# Front_Connector.net
KiCad netlist of a schematic drawn in Altium Designer
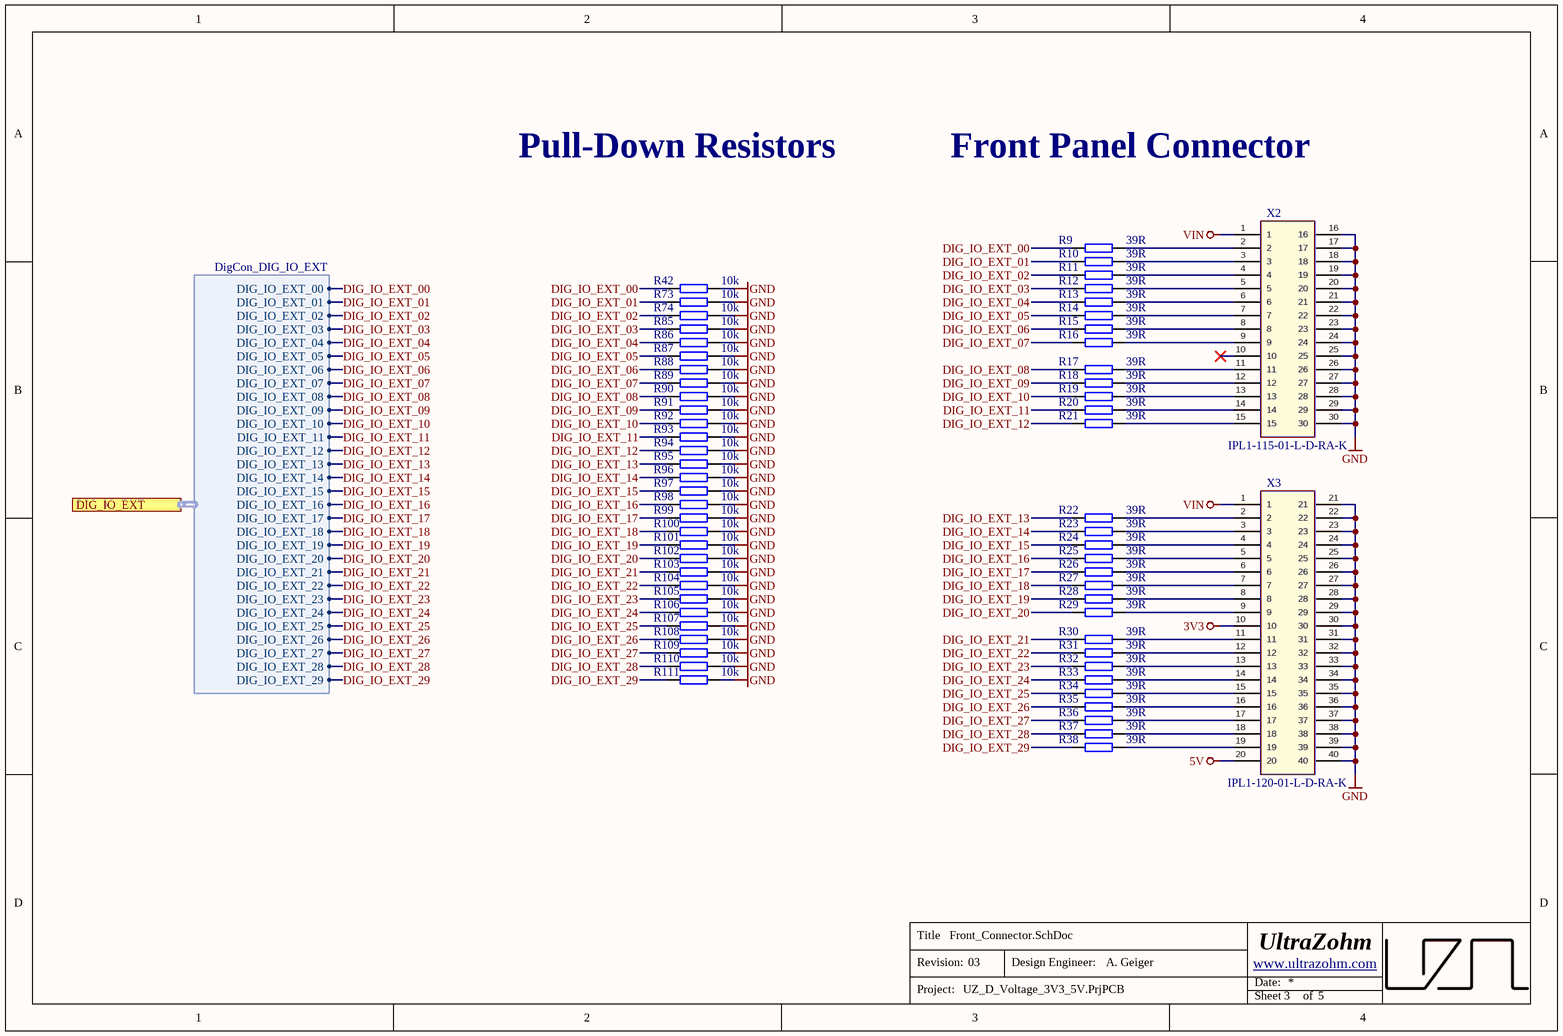
[diagram p0: Front_Connector.SchDoc]

(export (version "E")
  (design (tool "Eeschema 10.0.6"))
  (components
    (comp (ref "R9")
      (value "39R")
      (footprint "R_0603_TE")
      (description "Generic resistor")
      (fields
        (field (name "MANUFACTURER PART NUMBER") "UZgen_R_0603_39R")
        (field (name "MANUFACTURER") "UZgen")
        (field (name "CREATED FROM") "UZgenTool")
      )
      (libsource (lib "user") (part "RES"))
    )
    (comp (ref "R10")
      (value "39R")
      (footprint "R_0603_TE")
      (description "Generic resistor")
      (fields
        (field (name "MANUFACTURER PART NUMBER") "UZgen_R_0603_39R")
        (field (name "MANUFACTURER") "UZgen")
        (field (name "CREATED FROM") "UZgenTool")
      )
      (libsource (lib "user") (part "RES"))
    )
    (comp (ref "R11")
      (value "39R")
      (footprint "R_0603_TE")
      (description "Generic resistor")
      (fields
        (field (name "MANUFACTURER PART NUMBER") "UZgen_R_0603_39R")
        (field (name "MANUFACTURER") "UZgen")
        (field (name "CREATED FROM") "UZgenTool")
      )
      (libsource (lib "user") (part "RES"))
    )
    (comp (ref "R12")
      (value "39R")
      (footprint "R_0603_TE")
      (description "Generic resistor")
      (fields
        (field (name "MANUFACTURER PART NUMBER") "UZgen_R_0603_39R")
        (field (name "MANUFACTURER") "UZgen")
        (field (name "CREATED FROM") "UZgenTool")
      )
      (libsource (lib "user") (part "RES"))
    )
    (comp (ref "R13")
      (value "39R")
      (footprint "R_0603_TE")
      (description "Generic resistor")
      (fields
        (field (name "MANUFACTURER PART NUMBER") "UZgen_R_0603_39R")
        (field (name "MANUFACTURER") "UZgen")
        (field (name "CREATED FROM") "UZgenTool")
      )
      (libsource (lib "user") (part "RES"))
    )
    (comp (ref "R14")
      (value "39R")
      (footprint "R_0603_TE")
      (description "Generic resistor")
      (fields
        (field (name "MANUFACTURER PART NUMBER") "UZgen_R_0603_39R")
        (field (name "MANUFACTURER") "UZgen")
        (field (name "CREATED FROM") "UZgenTool")
      )
      (libsource (lib "user") (part "RES"))
    )
    (comp (ref "R15")
      (value "39R")
      (footprint "R_0603_TE")
      (description "Generic resistor")
      (fields
        (field (name "MANUFACTURER PART NUMBER") "UZgen_R_0603_39R")
        (field (name "MANUFACTURER") "UZgen")
        (field (name "CREATED FROM") "UZgenTool")
      )
      (libsource (lib "user") (part "RES"))
    )
    (comp (ref "R16")
      (value "39R")
      (footprint "R_0603_TE")
      (description "Generic resistor")
      (fields
        (field (name "MANUFACTURER PART NUMBER") "UZgen_R_0603_39R")
        (field (name "MANUFACTURER") "UZgen")
        (field (name "CREATED FROM") "UZgenTool")
      )
      (libsource (lib "user") (part "RES"))
    )
    (comp (ref "R17")
      (value "39R")
      (footprint "R_0603_TE")
      (description "Generic resistor")
      (fields
        (field (name "MANUFACTURER PART NUMBER") "UZgen_R_0603_39R")
        (field (name "MANUFACTURER") "UZgen")
        (field (name "CREATED FROM") "UZgenTool")
      )
      (libsource (lib "user") (part "RES"))
    )
    (comp (ref "R18")
      (value "39R")
      (footprint "R_0603_TE")
      (description "Generic resistor")
      (fields
        (field (name "MANUFACTURER PART NUMBER") "UZgen_R_0603_39R")
        (field (name "MANUFACTURER") "UZgen")
        (field (name "CREATED FROM") "UZgenTool")
      )
      (libsource (lib "user") (part "RES"))
    )
    (comp (ref "R19")
      (value "39R")
      (footprint "R_0603_TE")
      (description "Generic resistor")
      (fields
        (field (name "MANUFACTURER PART NUMBER") "UZgen_R_0603_39R")
        (field (name "MANUFACTURER") "UZgen")
        (field (name "CREATED FROM") "UZgenTool")
      )
      (libsource (lib "user") (part "RES"))
    )
    (comp (ref "R20")
      (value "39R")
      (footprint "R_0603_TE")
      (description "Generic resistor")
      (fields
        (field (name "MANUFACTURER PART NUMBER") "UZgen_R_0603_39R")
        (field (name "MANUFACTURER") "UZgen")
        (field (name "CREATED FROM") "UZgenTool")
      )
      (libsource (lib "user") (part "RES"))
    )
    (comp (ref "R21")
      (value "39R")
      (footprint "R_0603_TE")
      (description "Generic resistor")
      (fields
        (field (name "MANUFACTURER PART NUMBER") "UZgen_R_0603_39R")
        (field (name "MANUFACTURER") "UZgen")
        (field (name "CREATED FROM") "UZgenTool")
      )
      (libsource (lib "user") (part "RES"))
    )
    (comp (ref "R22")
      (value "39R")
      (footprint "R_0603_TE")
      (description "Generic resistor")
      (fields
        (field (name "MANUFACTURER PART NUMBER") "UZgen_R_0603_39R")
        (field (name "MANUFACTURER") "UZgen")
        (field (name "CREATED FROM") "UZgenTool")
      )
      (libsource (lib "user") (part "RES"))
    )
    (comp (ref "R23")
      (value "39R")
      (footprint "R_0603_TE")
      (description "Generic resistor")
      (fields
        (field (name "MANUFACTURER PART NUMBER") "UZgen_R_0603_39R")
        (field (name "MANUFACTURER") "UZgen")
        (field (name "CREATED FROM") "UZgenTool")
      )
      (libsource (lib "user") (part "RES"))
    )
    (comp (ref "R24")
      (value "39R")
      (footprint "R_0603_TE")
      (description "Generic resistor")
      (fields
        (field (name "MANUFACTURER PART NUMBER") "UZgen_R_0603_39R")
        (field (name "MANUFACTURER") "UZgen")
        (field (name "CREATED FROM") "UZgenTool")
      )
      (libsource (lib "user") (part "RES"))
    )
    (comp (ref "R25")
      (value "39R")
      (footprint "R_0603_TE")
      (description "Generic resistor")
      (fields
        (field (name "MANUFACTURER PART NUMBER") "UZgen_R_0603_39R")
        (field (name "MANUFACTURER") "UZgen")
        (field (name "CREATED FROM") "UZgenTool")
      )
      (libsource (lib "user") (part "RES"))
    )
    (comp (ref "R26")
      (value "39R")
      (footprint "R_0603_TE")
      (description "Generic resistor")
      (fields
        (field (name "MANUFACTURER PART NUMBER") "UZgen_R_0603_39R")
        (field (name "MANUFACTURER") "UZgen")
        (field (name "CREATED FROM") "UZgenTool")
      )
      (libsource (lib "user") (part "RES"))
    )
    (comp (ref "R27")
      (value "39R")
      (footprint "R_0603_TE")
      (description "Generic resistor")
      (fields
        (field (name "MANUFACTURER PART NUMBER") "UZgen_R_0603_39R")
        (field (name "MANUFACTURER") "UZgen")
        (field (name "CREATED FROM") "UZgenTool")
      )
      (libsource (lib "user") (part "RES"))
    )
    (comp (ref "R28")
      (value "39R")
      (footprint "R_0603_TE")
      (description "Generic resistor")
      (fields
        (field (name "MANUFACTURER PART NUMBER") "UZgen_R_0603_39R")
        (field (name "MANUFACTURER") "UZgen")
        (field (name "CREATED FROM") "UZgenTool")
      )
      (libsource (lib "user") (part "RES"))
    )
    (comp (ref "R29")
      (value "39R")
      (footprint "R_0603_TE")
      (description "Generic resistor")
      (fields
        (field (name "MANUFACTURER PART NUMBER") "UZgen_R_0603_39R")
        (field (name "MANUFACTURER") "UZgen")
        (field (name "CREATED FROM") "UZgenTool")
      )
      (libsource (lib "user") (part "RES"))
    )
    (comp (ref "R30")
      (value "39R")
      (footprint "R_0603_TE")
      (description "Generic resistor")
      (fields
        (field (name "MANUFACTURER PART NUMBER") "UZgen_R_0603_39R")
        (field (name "MANUFACTURER") "UZgen")
        (field (name "CREATED FROM") "UZgenTool")
      )
      (libsource (lib "user") (part "RES"))
    )
    (comp (ref "R31")
      (value "39R")
      (footprint "R_0603_TE")
      (description "Generic resistor")
      (fields
        (field (name "MANUFACTURER PART NUMBER") "UZgen_R_0603_39R")
        (field (name "MANUFACTURER") "UZgen")
        (field (name "CREATED FROM") "UZgenTool")
      )
      (libsource (lib "user") (part "RES"))
    )
    (comp (ref "R32")
      (value "39R")
      (footprint "R_0603_TE")
      (description "Generic resistor")
      (fields
        (field (name "MANUFACTURER PART NUMBER") "UZgen_R_0603_39R")
        (field (name "MANUFACTURER") "UZgen")
        (field (name "CREATED FROM") "UZgenTool")
      )
      (libsource (lib "user") (part "RES"))
    )
    (comp (ref "R33")
      (value "39R")
      (footprint "R_0603_TE")
      (description "Generic resistor")
      (fields
        (field (name "MANUFACTURER PART NUMBER") "UZgen_R_0603_39R")
        (field (name "MANUFACTURER") "UZgen")
        (field (name "CREATED FROM") "UZgenTool")
      )
      (libsource (lib "user") (part "RES"))
    )
    (comp (ref "R34")
      (value "39R")
      (footprint "R_0603_TE")
      (description "Generic resistor")
      (fields
        (field (name "MANUFACTURER PART NUMBER") "UZgen_R_0603_39R")
        (field (name "MANUFACTURER") "UZgen")
        (field (name "CREATED FROM") "UZgenTool")
      )
      (libsource (lib "user") (part "RES"))
    )
    (comp (ref "R35")
      (value "39R")
      (footprint "R_0603_TE")
      (description "Generic resistor")
      (fields
        (field (name "MANUFACTURER PART NUMBER") "UZgen_R_0603_39R")
        (field (name "MANUFACTURER") "UZgen")
        (field (name "CREATED FROM") "UZgenTool")
      )
      (libsource (lib "user") (part "RES"))
    )
    (comp (ref "R36")
      (value "39R")
      (footprint "R_0603_TE")
      (description "Generic resistor")
      (fields
        (field (name "MANUFACTURER PART NUMBER") "UZgen_R_0603_39R")
        (field (name "MANUFACTURER") "UZgen")
        (field (name "CREATED FROM") "UZgenTool")
      )
      (libsource (lib "user") (part "RES"))
    )
    (comp (ref "R37")
      (value "39R")
      (footprint "R_0603_TE")
      (description "Generic resistor")
      (fields
        (field (name "MANUFACTURER PART NUMBER") "UZgen_R_0603_39R")
        (field (name "MANUFACTURER") "UZgen")
        (field (name "CREATED FROM") "UZgenTool")
      )
      (libsource (lib "user") (part "RES"))
    )
    (comp (ref "R38")
      (value "39R")
      (footprint "R_0603_TE")
      (description "Generic resistor")
      (fields
        (field (name "MANUFACTURER PART NUMBER") "UZgen_R_0603_39R")
        (field (name "MANUFACTURER") "UZgen")
        (field (name "CREATED FROM") "UZgenTool")
      )
      (libsource (lib "user") (part "RES"))
    )
    (comp (ref "R42")
      (value "10k")
      (footprint "R_0603_TE")
      (description "Generic resistor")
      (fields
        (field (name "MANUFACTURER PART NUMBER") "UZgen_R_0603_10k")
        (field (name "MANUFACTURER") "UZgen")
        (field (name "CREATED FROM") "AGeiger")
      )
      (libsource (lib "user") (part "RES"))
    )
    (comp (ref "R73")
      (value "10k")
      (footprint "R_0603_TE")
      (description "Generic resistor")
      (fields
        (field (name "MANUFACTURER PART NUMBER") "UZgen_R_0603_10k")
        (field (name "MANUFACTURER") "UZgen")
        (field (name "CREATED FROM") "AGeiger")
      )
      (libsource (lib "user") (part "RES"))
    )
    (comp (ref "R74")
      (value "10k")
      (footprint "R_0603_TE")
      (description "Generic resistor")
      (fields
        (field (name "MANUFACTURER PART NUMBER") "UZgen_R_0603_10k")
        (field (name "MANUFACTURER") "UZgen")
        (field (name "CREATED FROM") "AGeiger")
      )
      (libsource (lib "user") (part "RES"))
    )
    (comp (ref "R85")
      (value "10k")
      (footprint "R_0603_TE")
      (description "Generic resistor")
      (fields
        (field (name "MANUFACTURER PART NUMBER") "UZgen_R_0603_10k")
        (field (name "MANUFACTURER") "UZgen")
        (field (name "CREATED FROM") "AGeiger")
      )
      (libsource (lib "user") (part "RES"))
    )
    (comp (ref "R86")
      (value "10k")
      (footprint "R_0603_TE")
      (description "Generic resistor")
      (fields
        (field (name "MANUFACTURER PART NUMBER") "UZgen_R_0603_10k")
        (field (name "MANUFACTURER") "UZgen")
        (field (name "CREATED FROM") "AGeiger")
      )
      (libsource (lib "user") (part "RES"))
    )
    (comp (ref "R87")
      (value "10k")
      (footprint "R_0603_TE")
      (description "Generic resistor")
      (fields
        (field (name "MANUFACTURER PART NUMBER") "UZgen_R_0603_10k")
        (field (name "MANUFACTURER") "UZgen")
        (field (name "CREATED FROM") "AGeiger")
      )
      (libsource (lib "user") (part "RES"))
    )
    (comp (ref "R88")
      (value "10k")
      (footprint "R_0603_TE")
      (description "Generic resistor")
      (fields
        (field (name "MANUFACTURER PART NUMBER") "UZgen_R_0603_10k")
        (field (name "MANUFACTURER") "UZgen")
        (field (name "CREATED FROM") "AGeiger")
      )
      (libsource (lib "user") (part "RES"))
    )
    (comp (ref "R89")
      (value "10k")
      (footprint "R_0603_TE")
      (description "Generic resistor")
      (fields
        (field (name "MANUFACTURER PART NUMBER") "UZgen_R_0603_10k")
        (field (name "MANUFACTURER") "UZgen")
        (field (name "CREATED FROM") "AGeiger")
      )
      (libsource (lib "user") (part "RES"))
    )
    (comp (ref "R90")
      (value "10k")
      (footprint "R_0603_TE")
      (description "Generic resistor")
      (fields
        (field (name "MANUFACTURER PART NUMBER") "UZgen_R_0603_10k")
        (field (name "MANUFACTURER") "UZgen")
        (field (name "CREATED FROM") "AGeiger")
      )
      (libsource (lib "user") (part "RES"))
    )
    (comp (ref "R91")
      (value "10k")
      (footprint "R_0603_TE")
      (description "Generic resistor")
      (fields
        (field (name "MANUFACTURER PART NUMBER") "UZgen_R_0603_10k")
        (field (name "MANUFACTURER") "UZgen")
        (field (name "CREATED FROM") "AGeiger")
      )
      (libsource (lib "user") (part "RES"))
    )
    (comp (ref "R92")
      (value "10k")
      (footprint "R_0603_TE")
      (description "Generic resistor")
      (fields
        (field (name "MANUFACTURER PART NUMBER") "UZgen_R_0603_10k")
        (field (name "MANUFACTURER") "UZgen")
        (field (name "CREATED FROM") "AGeiger")
      )
      (libsource (lib "user") (part "RES"))
    )
    (comp (ref "R93")
      (value "10k")
      (footprint "R_0603_TE")
      (description "Generic resistor")
      (fields
        (field (name "MANUFACTURER PART NUMBER") "UZgen_R_0603_10k")
        (field (name "MANUFACTURER") "UZgen")
        (field (name "CREATED FROM") "AGeiger")
      )
      (libsource (lib "user") (part "RES"))
    )
    (comp (ref "R94")
      (value "10k")
      (footprint "R_0603_TE")
      (description "Generic resistor")
      (fields
        (field (name "MANUFACTURER PART NUMBER") "UZgen_R_0603_10k")
        (field (name "MANUFACTURER") "UZgen")
        (field (name "CREATED FROM") "AGeiger")
      )
      (libsource (lib "user") (part "RES"))
    )
    (comp (ref "R95")
      (value "10k")
      (footprint "R_0603_TE")
      (description "Generic resistor")
      (fields
        (field (name "MANUFACTURER PART NUMBER") "UZgen_R_0603_10k")
        (field (name "MANUFACTURER") "UZgen")
        (field (name "CREATED FROM") "AGeiger")
      )
      (libsource (lib "user") (part "RES"))
    )
    (comp (ref "R96")
      (value "10k")
      (footprint "R_0603_TE")
      (description "Generic resistor")
      (fields
        (field (name "MANUFACTURER PART NUMBER") "UZgen_R_0603_10k")
        (field (name "MANUFACTURER") "UZgen")
        (field (name "CREATED FROM") "AGeiger")
      )
      (libsource (lib "user") (part "RES"))
    )
    (comp (ref "R97")
      (value "10k")
      (footprint "R_0603_TE")
      (description "Generic resistor")
      (fields
        (field (name "MANUFACTURER PART NUMBER") "UZgen_R_0603_10k")
        (field (name "MANUFACTURER") "UZgen")
        (field (name "CREATED FROM") "AGeiger")
      )
      (libsource (lib "user") (part "RES"))
    )
    (comp (ref "R98")
      (value "10k")
      (footprint "R_0603_TE")
      (description "Generic resistor")
      (fields
        (field (name "MANUFACTURER PART NUMBER") "UZgen_R_0603_10k")
        (field (name "MANUFACTURER") "UZgen")
        (field (name "CREATED FROM") "AGeiger")
      )
      (libsource (lib "user") (part "RES"))
    )
    (comp (ref "R99")
      (value "10k")
      (footprint "R_0603_TE")
      (description "Generic resistor")
      (fields
        (field (name "MANUFACTURER PART NUMBER") "UZgen_R_0603_10k")
        (field (name "MANUFACTURER") "UZgen")
        (field (name "CREATED FROM") "AGeiger")
      )
      (libsource (lib "user") (part "RES"))
    )
    (comp (ref "R100")
      (value "10k")
      (footprint "R_0603_TE")
      (description "Generic resistor")
      (fields
        (field (name "MANUFACTURER PART NUMBER") "UZgen_R_0603_10k")
        (field (name "MANUFACTURER") "UZgen")
        (field (name "CREATED FROM") "AGeiger")
      )
      (libsource (lib "user") (part "RES"))
    )
    (comp (ref "R101")
      (value "10k")
      (footprint "R_0603_TE")
      (description "Generic resistor")
      (fields
        (field (name "MANUFACTURER PART NUMBER") "UZgen_R_0603_10k")
        (field (name "MANUFACTURER") "UZgen")
        (field (name "CREATED FROM") "AGeiger")
      )
      (libsource (lib "user") (part "RES"))
    )
    (comp (ref "R102")
      (value "10k")
      (footprint "R_0603_TE")
      (description "Generic resistor")
      (fields
        (field (name "MANUFACTURER PART NUMBER") "UZgen_R_0603_10k")
        (field (name "MANUFACTURER") "UZgen")
        (field (name "CREATED FROM") "AGeiger")
      )
      (libsource (lib "user") (part "RES"))
    )
    (comp (ref "R103")
      (value "10k")
      (footprint "R_0603_TE")
      (description "Generic resistor")
      (fields
        (field (name "MANUFACTURER PART NUMBER") "UZgen_R_0603_10k")
        (field (name "MANUFACTURER") "UZgen")
        (field (name "CREATED FROM") "AGeiger")
      )
      (libsource (lib "user") (part "RES"))
    )
    (comp (ref "R104")
      (value "10k")
      (footprint "R_0603_TE")
      (description "Generic resistor")
      (fields
        (field (name "MANUFACTURER PART NUMBER") "UZgen_R_0603_10k")
        (field (name "MANUFACTURER") "UZgen")
        (field (name "CREATED FROM") "AGeiger")
      )
      (libsource (lib "user") (part "RES"))
    )
    (comp (ref "R105")
      (value "10k")
      (footprint "R_0603_TE")
      (description "Generic resistor")
      (fields
        (field (name "MANUFACTURER PART NUMBER") "UZgen_R_0603_10k")
        (field (name "MANUFACTURER") "UZgen")
        (field (name "CREATED FROM") "AGeiger")
      )
      (libsource (lib "user") (part "RES"))
    )
    (comp (ref "R106")
      (value "10k")
      (footprint "R_0603_TE")
      (description "Generic resistor")
      (fields
        (field (name "MANUFACTURER PART NUMBER") "UZgen_R_0603_10k")
        (field (name "MANUFACTURER") "UZgen")
        (field (name "CREATED FROM") "AGeiger")
      )
      (libsource (lib "user") (part "RES"))
    )
    (comp (ref "R107")
      (value "10k")
      (footprint "R_0603_TE")
      (description "Generic resistor")
      (fields
        (field (name "MANUFACTURER PART NUMBER") "UZgen_R_0603_10k")
        (field (name "MANUFACTURER") "UZgen")
        (field (name "CREATED FROM") "AGeiger")
      )
      (libsource (lib "user") (part "RES"))
    )
    (comp (ref "R108")
      (value "10k")
      (footprint "R_0603_TE")
      (description "Generic resistor")
      (fields
        (field (name "MANUFACTURER PART NUMBER") "UZgen_R_0603_10k")
        (field (name "MANUFACTURER") "UZgen")
        (field (name "CREATED FROM") "AGeiger")
      )
      (libsource (lib "user") (part "RES"))
    )
    (comp (ref "R109")
      (value "10k")
      (footprint "R_0603_TE")
      (description "Generic resistor")
      (fields
        (field (name "MANUFACTURER PART NUMBER") "UZgen_R_0603_10k")
        (field (name "MANUFACTURER") "UZgen")
        (field (name "CREATED FROM") "AGeiger")
      )
      (libsource (lib "user") (part "RES"))
    )
    (comp (ref "R110")
      (value "10k")
      (footprint "R_0603_TE")
      (description "Generic resistor")
      (fields
        (field (name "MANUFACTURER PART NUMBER") "UZgen_R_0603_10k")
        (field (name "MANUFACTURER") "UZgen")
        (field (name "CREATED FROM") "AGeiger")
      )
      (libsource (lib "user") (part "RES"))
    )
    (comp (ref "R111")
      (value "10k")
      (footprint "R_0603_TE")
      (description "Generic resistor")
      (fields
        (field (name "MANUFACTURER PART NUMBER") "UZgen_R_0603_10k")
        (field (name "MANUFACTURER") "UZgen")
        (field (name "CREATED FROM") "AGeiger")
      )
      (libsource (lib "user") (part "RES"))
    )
    (comp (ref "X2")
      (value "IPL1-115-01-L-D-RA-K")
      (footprint "IPL1-115-01-XX-D-RA")
      (description "Terminal Assembly, Double Row, Right Angle, Thru-Hole, 2.54 mm x 2.54 mm Pitch, 30 Pins")
      (fields (field (name "MANUFACTURER") "SAMTEC") (field (name "CREATED FROM") "TWendt"))
      (libsource (lib "user") (part "IPL1-115-01-XX-D-RA"))
    )
    (comp (ref "X3")
      (value "IPL1-120-01-L-D-RA-K")
      (footprint "IPL1-120-01-XX-D-RA")
      (description "Terminal Assembly, Double Row, Right Angle, Thru-Hole, 2.54 mm x 2.54 mm Pitch, 40 Pins")
      (fields (field (name "MANUFACTURER") "SAMTEC") (field (name "CREATED FROM") "TWendt"))
      (libsource (lib "user") (part "IPL1-120-01-XX-D-RA"))
    )
  )
  (nets
    (net (code "2") (name "/DIG_IO_EXT_00") (class "Default")
      (node (ref "R42") (pin "1") (pinfunction "1_1") (pintype "passive"))
      (node (ref "R9") (pin "1") (pinfunction "1_1") (pintype "passive"))
    )
    (net (code "3") (name "/DIG_IO_EXT_01") (class "Default")
      (node (ref "R10") (pin "1") (pinfunction "1_1") (pintype "passive"))
      (node (ref "R73") (pin "1") (pinfunction "1_1") (pintype "passive"))
    )
    (net (code "4") (name "/DIG_IO_EXT_02") (class "Default")
      (node (ref "R11") (pin "1") (pinfunction "1_1") (pintype "passive"))
      (node (ref "R74") (pin "1") (pinfunction "1_1") (pintype "passive"))
    )
    (net (code "5") (name "/DIG_IO_EXT_03") (class "Default")
      (node (ref "R12") (pin "1") (pinfunction "1_1") (pintype "passive"))
      (node (ref "R85") (pin "1") (pinfunction "1_1") (pintype "passive"))
    )
    (net (code "6") (name "/DIG_IO_EXT_04") (class "Default")
      (node (ref "R13") (pin "1") (pinfunction "1_1") (pintype "passive"))
      (node (ref "R86") (pin "1") (pinfunction "1_1") (pintype "passive"))
    )
    (net (code "7") (name "/DIG_IO_EXT_05") (class "Default")
      (node (ref "R14") (pin "1") (pinfunction "1_1") (pintype "passive"))
      (node (ref "R87") (pin "1") (pinfunction "1_1") (pintype "passive"))
    )
    (net (code "8") (name "/DIG_IO_EXT_06") (class "Default")
      (node (ref "R15") (pin "1") (pinfunction "1_1") (pintype "passive"))
      (node (ref "R88") (pin "1") (pinfunction "1_1") (pintype "passive"))
    )
    (net (code "9") (name "/DIG_IO_EXT_07") (class "Default")
      (node (ref "R16") (pin "1") (pinfunction "1_1") (pintype "passive"))
      (node (ref "R89") (pin "1") (pinfunction "1_1") (pintype "passive"))
    )
    (net (code "10") (name "/DIG_IO_EXT_08") (class "Default")
      (node (ref "R17") (pin "1") (pinfunction "1_1") (pintype "passive"))
      (node (ref "R90") (pin "1") (pinfunction "1_1") (pintype "passive"))
    )
    (net (code "11") (name "/DIG_IO_EXT_09") (class "Default")
      (node (ref "R18") (pin "1") (pinfunction "1_1") (pintype "passive"))
      (node (ref "R91") (pin "1") (pinfunction "1_1") (pintype "passive"))
    )
    (net (code "12") (name "/DIG_IO_EXT_10") (class "Default")
      (node (ref "R19") (pin "1") (pinfunction "1_1") (pintype "passive"))
      (node (ref "R92") (pin "1") (pinfunction "1_1") (pintype "passive"))
    )
    (net (code "13") (name "/DIG_IO_EXT_11") (class "Default")
      (node (ref "R20") (pin "1") (pinfunction "1_1") (pintype "passive"))
      (node (ref "R93") (pin "1") (pinfunction "1_1") (pintype "passive"))
    )
    (net (code "14") (name "/DIG_IO_EXT_12") (class "Default")
      (node (ref "R21") (pin "1") (pinfunction "1_1") (pintype "passive"))
      (node (ref "R94") (pin "1") (pinfunction "1_1") (pintype "passive"))
    )
    (net (code "15") (name "/DIG_IO_EXT_13") (class "Default")
      (node (ref "R22") (pin "1") (pinfunction "1_1") (pintype "passive"))
      (node (ref "R95") (pin "1") (pinfunction "1_1") (pintype "passive"))
    )
    (net (code "16") (name "/DIG_IO_EXT_14") (class "Default")
      (node (ref "R23") (pin "1") (pinfunction "1_1") (pintype "passive"))
      (node (ref "R96") (pin "1") (pinfunction "1_1") (pintype "passive"))
    )
    (net (code "17") (name "/DIG_IO_EXT_15") (class "Default")
      (node (ref "R24") (pin "1") (pinfunction "1_1") (pintype "passive"))
      (node (ref "R97") (pin "1") (pinfunction "1_1") (pintype "passive"))
    )
    (net (code "18") (name "/DIG_IO_EXT_16") (class "Default")
      (node (ref "R25") (pin "1") (pinfunction "1_1") (pintype "passive"))
      (node (ref "R98") (pin "1") (pinfunction "1_1") (pintype "passive"))
    )
    (net (code "19") (name "/DIG_IO_EXT_17") (class "Default")
      (node (ref "R26") (pin "1") (pinfunction "1_1") (pintype "passive"))
      (node (ref "R99") (pin "1") (pinfunction "1_1") (pintype "passive"))
    )
    (net (code "20") (name "/DIG_IO_EXT_18") (class "Default")
      (node (ref "R100") (pin "1") (pinfunction "1_1") (pintype "passive"))
      (node (ref "R27") (pin "1") (pinfunction "1_1") (pintype "passive"))
    )
    (net (code "21") (name "/DIG_IO_EXT_19") (class "Default")
      (node (ref "R101") (pin "1") (pinfunction "1_1") (pintype "passive"))
      (node (ref "R28") (pin "1") (pinfunction "1_1") (pintype "passive"))
    )
    (net (code "22") (name "/DIG_IO_EXT_20") (class "Default")
      (node (ref "R102") (pin "1") (pinfunction "1_1") (pintype "passive"))
      (node (ref "R29") (pin "1") (pinfunction "1_1") (pintype "passive"))
    )
    (net (code "23") (name "/DIG_IO_EXT_21") (class "Default")
      (node (ref "R103") (pin "1") (pinfunction "1_1") (pintype "passive"))
      (node (ref "R30") (pin "1") (pinfunction "1_1") (pintype "passive"))
    )
    (net (code "24") (name "/DIG_IO_EXT_22") (class "Default")
      (node (ref "R104") (pin "1") (pinfunction "1_1") (pintype "passive"))
      (node (ref "R31") (pin "1") (pinfunction "1_1") (pintype "passive"))
    )
    (net (code "25") (name "/DIG_IO_EXT_23") (class "Default")
      (node (ref "R105") (pin "1") (pinfunction "1_1") (pintype "passive"))
      (node (ref "R32") (pin "1") (pinfunction "1_1") (pintype "passive"))
    )
    (net (code "26") (name "/DIG_IO_EXT_24") (class "Default")
      (node (ref "R106") (pin "1") (pinfunction "1_1") (pintype "passive"))
      (node (ref "R33") (pin "1") (pinfunction "1_1") (pintype "passive"))
    )
    (net (code "27") (name "/DIG_IO_EXT_25") (class "Default")
      (node (ref "R107") (pin "1") (pinfunction "1_1") (pintype "passive"))
      (node (ref "R34") (pin "1") (pinfunction "1_1") (pintype "passive"))
    )
    (net (code "28") (name "/DIG_IO_EXT_26") (class "Default")
      (node (ref "R108") (pin "1") (pinfunction "1_1") (pintype "passive"))
      (node (ref "R35") (pin "1") (pinfunction "1_1") (pintype "passive"))
    )
    (net (code "29") (name "/DIG_IO_EXT_27") (class "Default")
      (node (ref "R109") (pin "1") (pinfunction "1_1") (pintype "passive"))
      (node (ref "R36") (pin "1") (pinfunction "1_1") (pintype "passive"))
    )
    (net (code "30") (name "/DIG_IO_EXT_28") (class "Default")
      (node (ref "R110") (pin "1") (pinfunction "1_1") (pintype "passive"))
      (node (ref "R37") (pin "1") (pinfunction "1_1") (pintype "passive"))
    )
    (net (code "31") (name "/DIG_IO_EXT_29") (class "Default")
      (node (ref "R111") (pin "1") (pinfunction "1_1") (pintype "passive"))
      (node (ref "R38") (pin "1") (pinfunction "1_1") (pintype "passive"))
    )
    (net (code "33") (name "3V3") (class "Default")
      (node (ref "X3") (pin "10") (pinfunction "10_10") (pintype "passive"))
    )
    (net (code "34") (name "5V") (class "Default")
      (node (ref "X3") (pin "20") (pinfunction "20_20") (pintype "passive"))
    )
    (net (code "35") (name "GND") (class "Default")
      (node (ref "R100") (pin "2") (pinfunction "2_2") (pintype "passive"))
      (node (ref "R101") (pin "2") (pinfunction "2_2") (pintype "passive"))
      (node (ref "R102") (pin "2") (pinfunction "2_2") (pintype "passive"))
      (node (ref "R103") (pin "2") (pinfunction "2_2") (pintype "passive"))
      (node (ref "R104") (pin "2") (pinfunction "2_2") (pintype "passive"))
      (node (ref "R105") (pin "2") (pinfunction "2_2") (pintype "passive"))
      (node (ref "R106") (pin "2") (pinfunction "2_2") (pintype "passive"))
      (node (ref "R107") (pin "2") (pinfunction "2_2") (pintype "passive"))
      (node (ref "R108") (pin "2") (pinfunction "2_2") (pintype "passive"))
      (node (ref "R109") (pin "2") (pinfunction "2_2") (pintype "passive"))
      (node (ref "R110") (pin "2") (pinfunction "2_2") (pintype "passive"))
      (node (ref "R111") (pin "2") (pinfunction "2_2") (pintype "passive"))
      (node (ref "R42") (pin "2") (pinfunction "2_2") (pintype "passive"))
      (node (ref "R73") (pin "2") (pinfunction "2_2") (pintype "passive"))
      (node (ref "R74") (pin "2") (pinfunction "2_2") (pintype "passive"))
      (node (ref "R85") (pin "2") (pinfunction "2_2") (pintype "passive"))
      (node (ref "R86") (pin "2") (pinfunction "2_2") (pintype "passive"))
      (node (ref "R87") (pin "2") (pinfunction "2_2") (pintype "passive"))
      (node (ref "R88") (pin "2") (pinfunction "2_2") (pintype "passive"))
      (node (ref "R89") (pin "2") (pinfunction "2_2") (pintype "passive"))
      (node (ref "R90") (pin "2") (pinfunction "2_2") (pintype "passive"))
      (node (ref "R91") (pin "2") (pinfunction "2_2") (pintype "passive"))
      (node (ref "R92") (pin "2") (pinfunction "2_2") (pintype "passive"))
      (node (ref "R93") (pin "2") (pinfunction "2_2") (pintype "passive"))
      (node (ref "R94") (pin "2") (pinfunction "2_2") (pintype "passive"))
      (node (ref "R95") (pin "2") (pinfunction "2_2") (pintype "passive"))
      (node (ref "R96") (pin "2") (pinfunction "2_2") (pintype "passive"))
      (node (ref "R97") (pin "2") (pinfunction "2_2") (pintype "passive"))
      (node (ref "R98") (pin "2") (pinfunction "2_2") (pintype "passive"))
      (node (ref "R99") (pin "2") (pinfunction "2_2") (pintype "passive"))
      (node (ref "X2") (pin "16") (pinfunction "16_16") (pintype "passive"))
      (node (ref "X2") (pin "17") (pinfunction "17_17") (pintype "passive"))
      (node (ref "X2") (pin "18") (pinfunction "18_18") (pintype "passive"))
      (node (ref "X2") (pin "19") (pinfunction "19_19") (pintype "passive"))
      (node (ref "X2") (pin "20") (pinfunction "20_20") (pintype "passive"))
      (node (ref "X2") (pin "21") (pinfunction "21_21") (pintype "passive"))
      (node (ref "X2") (pin "22") (pinfunction "22_22") (pintype "passive"))
      (node (ref "X2") (pin "23") (pinfunction "23_23") (pintype "passive"))
      (node (ref "X2") (pin "24") (pinfunction "24_24") (pintype "passive"))
      (node (ref "X2") (pin "25") (pinfunction "25_25") (pintype "passive"))
      (node (ref "X2") (pin "26") (pinfunction "26_26") (pintype "passive"))
      (node (ref "X2") (pin "27") (pinfunction "27_27") (pintype "passive"))
      (node (ref "X2") (pin "28") (pinfunction "28_28") (pintype "passive"))
      (node (ref "X2") (pin "29") (pinfunction "29_29") (pintype "passive"))
      (node (ref "X2") (pin "30") (pinfunction "30_30") (pintype "passive"))
      (node (ref "X3") (pin "21") (pinfunction "21_21") (pintype "passive"))
      (node (ref "X3") (pin "22") (pinfunction "22_22") (pintype "passive"))
      (node (ref "X3") (pin "23") (pinfunction "23_23") (pintype "passive"))
      (node (ref "X3") (pin "24") (pinfunction "24_24") (pintype "passive"))
      (node (ref "X3") (pin "25") (pinfunction "25_25") (pintype "passive"))
      (node (ref "X3") (pin "26") (pinfunction "26_26") (pintype "passive"))
      (node (ref "X3") (pin "27") (pinfunction "27_27") (pintype "passive"))
      (node (ref "X3") (pin "28") (pinfunction "28_28") (pintype "passive"))
      (node (ref "X3") (pin "29") (pinfunction "29_29") (pintype "passive"))
      (node (ref "X3") (pin "30") (pinfunction "30_30") (pintype "passive"))
      (node (ref "X3") (pin "31") (pinfunction "31_31") (pintype "passive"))
      (node (ref "X3") (pin "32") (pinfunction "32_32") (pintype "passive"))
      (node (ref "X3") (pin "33") (pinfunction "33_33") (pintype "passive"))
      (node (ref "X3") (pin "34") (pinfunction "34_34") (pintype "passive"))
      (node (ref "X3") (pin "35") (pinfunction "35_35") (pintype "passive"))
      (node (ref "X3") (pin "36") (pinfunction "36_36") (pintype "passive"))
      (node (ref "X3") (pin "37") (pinfunction "37_37") (pintype "passive"))
      (node (ref "X3") (pin "38") (pinfunction "38_38") (pintype "passive"))
      (node (ref "X3") (pin "39") (pinfunction "39_39") (pintype "passive"))
      (node (ref "X3") (pin "40") (pinfunction "40_40") (pintype "passive"))
    )
    (net (code "36") (name "Net-(R9-Pad2)") (class "Default")
      (node (ref "R9") (pin "2") (pinfunction "2_2") (pintype "passive"))
      (node (ref "X2") (pin "2") (pinfunction "2_2") (pintype "passive"))
    )
    (net (code "37") (name "Net-(R10-Pad2)") (class "Default")
      (node (ref "R10") (pin "2") (pinfunction "2_2") (pintype "passive"))
      (node (ref "X2") (pin "3") (pinfunction "3_3") (pintype "passive"))
    )
    (net (code "38") (name "Net-(R11-Pad2)") (class "Default")
      (node (ref "R11") (pin "2") (pinfunction "2_2") (pintype "passive"))
      (node (ref "X2") (pin "4") (pinfunction "4_4") (pintype "passive"))
    )
    (net (code "39") (name "Net-(R12-Pad2)") (class "Default")
      (node (ref "R12") (pin "2") (pinfunction "2_2") (pintype "passive"))
      (node (ref "X2") (pin "5") (pinfunction "5_5") (pintype "passive"))
    )
    (net (code "40") (name "Net-(R13-Pad2)") (class "Default")
      (node (ref "R13") (pin "2") (pinfunction "2_2") (pintype "passive"))
      (node (ref "X2") (pin "6") (pinfunction "6_6") (pintype "passive"))
    )
    (net (code "41") (name "Net-(R14-Pad2)") (class "Default")
      (node (ref "R14") (pin "2") (pinfunction "2_2") (pintype "passive"))
      (node (ref "X2") (pin "7") (pinfunction "7_7") (pintype "passive"))
    )
    (net (code "42") (name "Net-(R15-Pad2)") (class "Default")
      (node (ref "R15") (pin "2") (pinfunction "2_2") (pintype "passive"))
      (node (ref "X2") (pin "8") (pinfunction "8_8") (pintype "passive"))
    )
    (net (code "43") (name "Net-(R16-Pad2)") (class "Default")
      (node (ref "R16") (pin "2") (pinfunction "2_2") (pintype "passive"))
      (node (ref "X2") (pin "9") (pinfunction "9_9") (pintype "passive"))
    )
    (net (code "44") (name "Net-(R17-Pad2)") (class "Default")
      (node (ref "R17") (pin "2") (pinfunction "2_2") (pintype "passive"))
      (node (ref "X2") (pin "11") (pinfunction "11_11") (pintype "passive"))
    )
    (net (code "45") (name "Net-(R18-Pad2)") (class "Default")
      (node (ref "R18") (pin "2") (pinfunction "2_2") (pintype "passive"))
      (node (ref "X2") (pin "12") (pinfunction "12_12") (pintype "passive"))
    )
    (net (code "46") (name "Net-(R19-Pad2)") (class "Default")
      (node (ref "R19") (pin "2") (pinfunction "2_2") (pintype "passive"))
      (node (ref "X2") (pin "13") (pinfunction "13_13") (pintype "passive"))
    )
    (net (code "47") (name "Net-(R20-Pad2)") (class "Default")
      (node (ref "R20") (pin "2") (pinfunction "2_2") (pintype "passive"))
      (node (ref "X2") (pin "14") (pinfunction "14_14") (pintype "passive"))
    )
    (net (code "48") (name "Net-(R21-Pad2)") (class "Default")
      (node (ref "R21") (pin "2") (pinfunction "2_2") (pintype "passive"))
      (node (ref "X2") (pin "15") (pinfunction "15_15") (pintype "passive"))
    )
    (net (code "49") (name "Net-(R22-Pad2)") (class "Default")
      (node (ref "R22") (pin "2") (pinfunction "2_2") (pintype "passive"))
      (node (ref "X3") (pin "2") (pinfunction "2_2") (pintype "passive"))
    )
    (net (code "50") (name "Net-(R23-Pad2)") (class "Default")
      (node (ref "R23") (pin "2") (pinfunction "2_2") (pintype "passive"))
      (node (ref "X3") (pin "3") (pinfunction "3_3") (pintype "passive"))
    )
    (net (code "51") (name "Net-(R24-Pad2)") (class "Default")
      (node (ref "R24") (pin "2") (pinfunction "2_2") (pintype "passive"))
      (node (ref "X3") (pin "4") (pinfunction "4_4") (pintype "passive"))
    )
    (net (code "52") (name "Net-(R25-Pad2)") (class "Default")
      (node (ref "R25") (pin "2") (pinfunction "2_2") (pintype "passive"))
      (node (ref "X3") (pin "5") (pinfunction "5_5") (pintype "passive"))
    )
    (net (code "53") (name "Net-(R26-Pad2)") (class "Default")
      (node (ref "R26") (pin "2") (pinfunction "2_2") (pintype "passive"))
      (node (ref "X3") (pin "6") (pinfunction "6_6") (pintype "passive"))
    )
    (net (code "54") (name "Net-(R27-Pad2)") (class "Default")
      (node (ref "R27") (pin "2") (pinfunction "2_2") (pintype "passive"))
      (node (ref "X3") (pin "7") (pinfunction "7_7") (pintype "passive"))
    )
    (net (code "55") (name "Net-(R28-Pad2)") (class "Default")
      (node (ref "R28") (pin "2") (pinfunction "2_2") (pintype "passive"))
      (node (ref "X3") (pin "8") (pinfunction "8_8") (pintype "passive"))
    )
    (net (code "56") (name "Net-(R29-Pad2)") (class "Default")
      (node (ref "R29") (pin "2") (pinfunction "2_2") (pintype "passive"))
      (node (ref "X3") (pin "9") (pinfunction "9_9") (pintype "passive"))
    )
    (net (code "57") (name "Net-(R30-Pad2)") (class "Default")
      (node (ref "R30") (pin "2") (pinfunction "2_2") (pintype "passive"))
      (node (ref "X3") (pin "11") (pinfunction "11_11") (pintype "passive"))
    )
    (net (code "58") (name "Net-(R31-Pad2)") (class "Default")
      (node (ref "R31") (pin "2") (pinfunction "2_2") (pintype "passive"))
      (node (ref "X3") (pin "12") (pinfunction "12_12") (pintype "passive"))
    )
    (net (code "59") (name "Net-(R32-Pad2)") (class "Default")
      (node (ref "R32") (pin "2") (pinfunction "2_2") (pintype "passive"))
      (node (ref "X3") (pin "13") (pinfunction "13_13") (pintype "passive"))
    )
    (net (code "60") (name "Net-(R33-Pad2)") (class "Default")
      (node (ref "R33") (pin "2") (pinfunction "2_2") (pintype "passive"))
      (node (ref "X3") (pin "14") (pinfunction "14_14") (pintype "passive"))
    )
    (net (code "61") (name "Net-(R34-Pad2)") (class "Default")
      (node (ref "R34") (pin "2") (pinfunction "2_2") (pintype "passive"))
      (node (ref "X3") (pin "15") (pinfunction "15_15") (pintype "passive"))
    )
    (net (code "62") (name "Net-(R35-Pad2)") (class "Default")
      (node (ref "R35") (pin "2") (pinfunction "2_2") (pintype "passive"))
      (node (ref "X3") (pin "16") (pinfunction "16_16") (pintype "passive"))
    )
    (net (code "63") (name "Net-(R36-Pad2)") (class "Default")
      (node (ref "R36") (pin "2") (pinfunction "2_2") (pintype "passive"))
      (node (ref "X3") (pin "17") (pinfunction "17_17") (pintype "passive"))
    )
    (net (code "64") (name "Net-(R37-Pad2)") (class "Default")
      (node (ref "R37") (pin "2") (pinfunction "2_2") (pintype "passive"))
      (node (ref "X3") (pin "18") (pinfunction "18_18") (pintype "passive"))
    )
    (net (code "65") (name "Net-(R38-Pad2)") (class "Default")
      (node (ref "R38") (pin "2") (pinfunction "2_2") (pintype "passive"))
      (node (ref "X3") (pin "19") (pinfunction "19_19") (pintype "passive"))
    )
    (net (code "66") (name "VIN") (class "Default")
      (node (ref "X2") (pin "1") (pinfunction "1_1") (pintype "passive"))
      (node (ref "X3") (pin "1") (pinfunction "1_1") (pintype "passive"))
    )
    (net (code "67") (name "unconnected-(X2-Pad10)") (class "Default")
      (node (ref "X2") (pin "10") (pinfunction "10_10") (pintype "passive+no_connect"))
    )
  )
)
